# attinier85-power-shield-mk-1_0.net
KiCad netlist of a schematic drawn in EAGLE
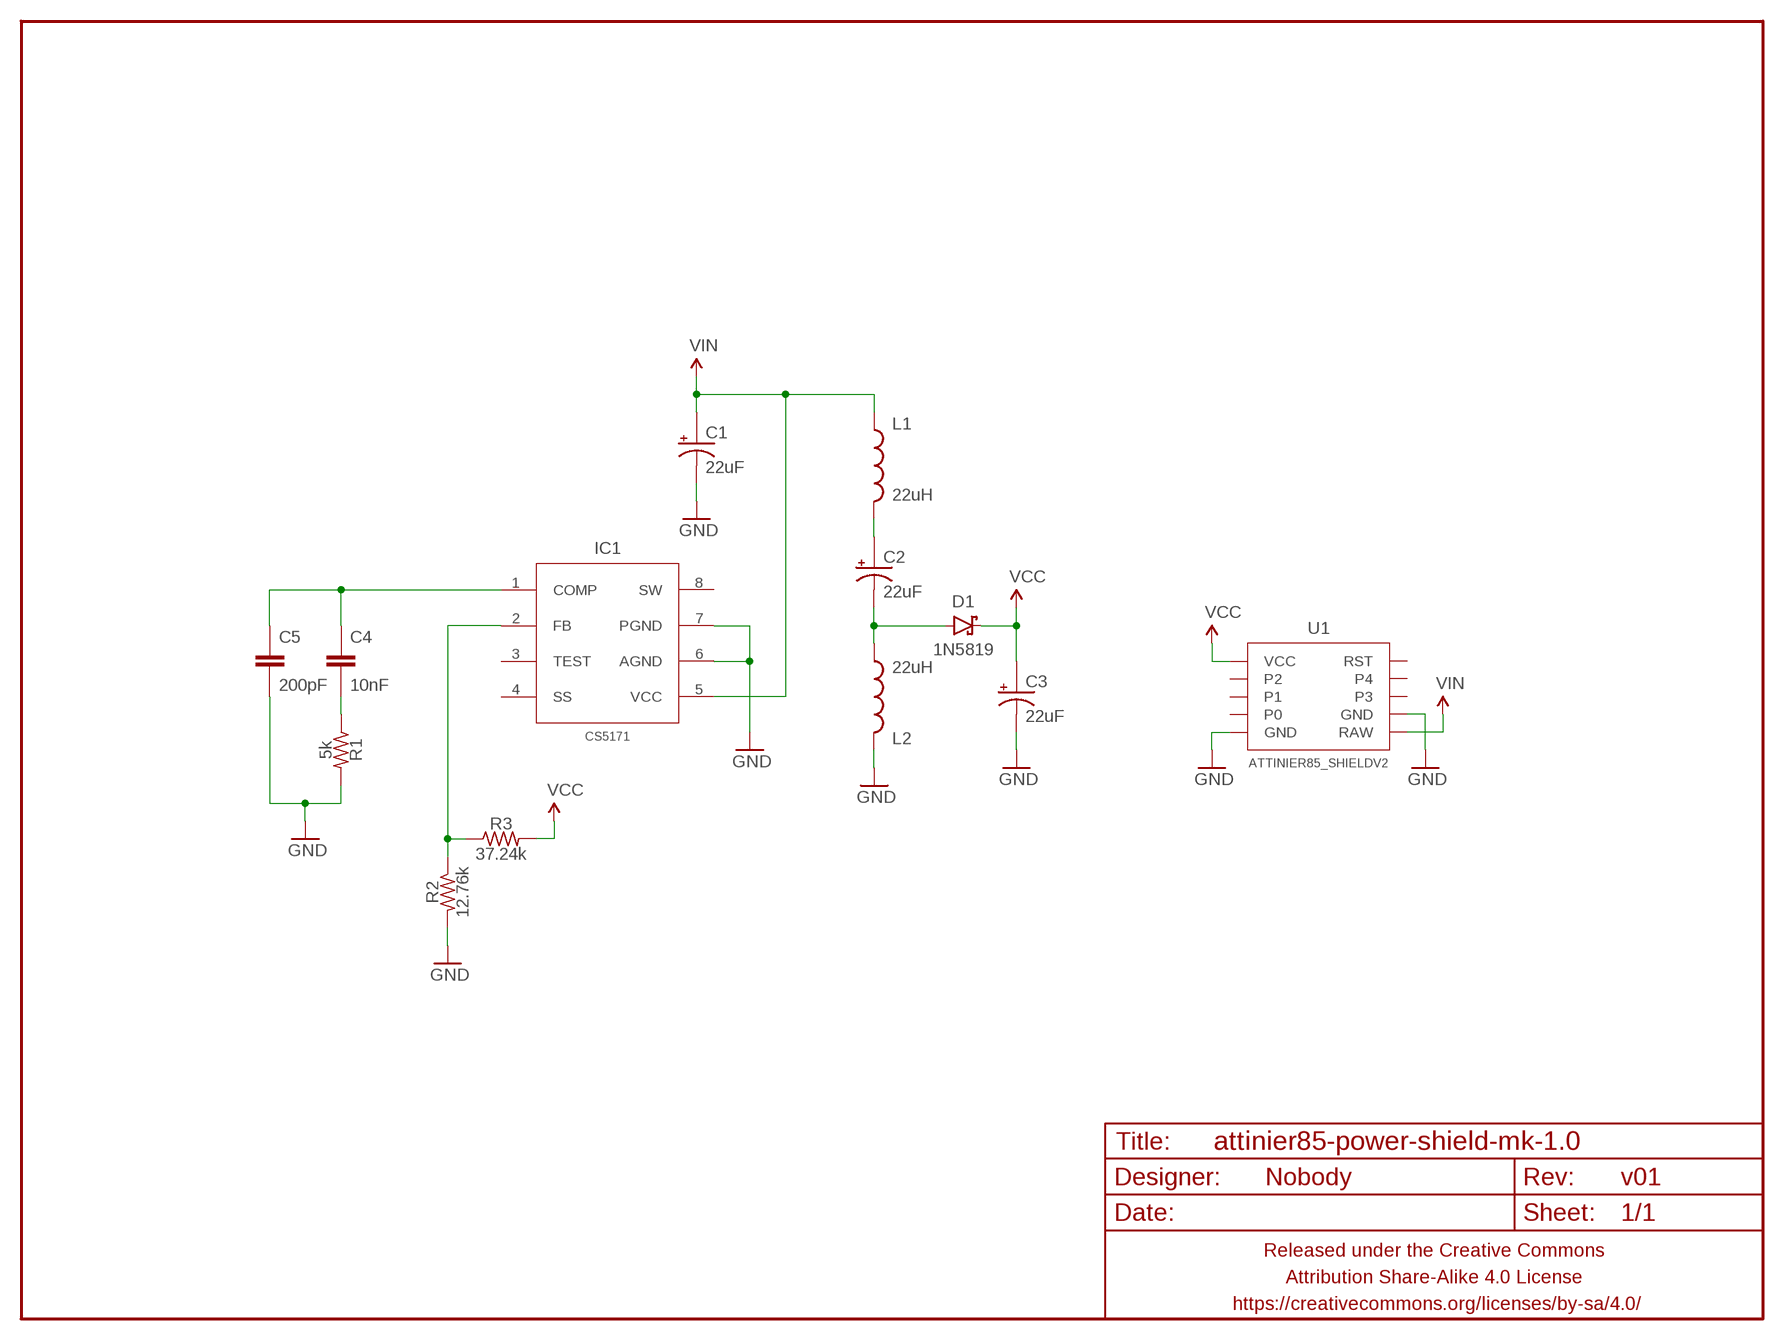
[diagram p0: schematic, sheet 1]

(export (version "E")
  (design (tool "Eeschema 10.0.6"))
  (components
    (comp (ref "C1")
      (value "22uF")
      (footprint "eagle-import:E2,5-6")
      (libsource (lib "eagle-import") (part "CAPACITOR-POLARIZEDE2.5-6"))
    )
    (comp (ref "C2")
      (value "22uF")
      (footprint "eagle-import:E2,5-6")
      (libsource (lib "eagle-import") (part "CAPACITOR-POLARIZEDE2.5-6"))
    )
    (comp (ref "C3")
      (value "22uF")
      (footprint "eagle-import:E2,5-6")
      (libsource (lib "eagle-import") (part "CAPACITOR-POLARIZEDE2.5-6"))
    )
    (comp (ref "C4")
      (value "10nF")
      (footprint "eagle-import:C025-024X044")
      (libsource (lib "eagle-import") (part "CAPACITOR-CERAMIC025-024X044"))
    )
    (comp (ref "C5")
      (value "200pF")
      (footprint "eagle-import:C025-024X044")
      (libsource (lib "eagle-import") (part "CAPACITOR-CERAMIC025-024X044"))
    )
    (comp (ref "D1")
      (value "1N5819")
      (footprint "eagle-import:DIODE-10.16MM")
      (libsource (lib "eagle-import") (part "DIODE-SCHOTTKYPTH-10.16MM"))
    )
    (comp (ref "FRAME1")
      (value "FRAME-LETTERNO_PACKAGE")
      (footprint "eagle-import:DUMMY")
      (fields (field (name "DESIGNER") "Nobody"))
      (libsource (lib "eagle-import") (part "FRAME-LETTERNO_PACKAGE"))
    )
    (comp (ref "IC1")
      (value "CS5171")
      (footprint "eagle-import:SO08")
      (libsource (lib "eagle-import") (part "CS5171/3SOIC-CS5171"))
    )
    (comp (ref "L1")
      (value "22uH")
      (footprint "eagle-import:INDUCTOR-AXIAL-PTH-10.16MM")
      (libsource (lib "eagle-import") (part "INDUCTORAXIAL-PTH-10.16MM"))
    )
    (comp (ref "L2")
      (value "22uH")
      (footprint "eagle-import:INDUCTOR-AXIAL-PTH-10.16MM")
      (libsource (lib "eagle-import") (part "INDUCTORAXIAL-PTH-10.16MM"))
    )
    (comp (ref "R1")
      (value "5k")
      (footprint "eagle-import:RESISTOR-AXIAL-PTH-6.35MM")
      (libsource (lib "eagle-import") (part "RESISTORPTH-AXIAL-6.35MM"))
    )
    (comp (ref "R2")
      (value "12.76k")
      (footprint "eagle-import:RESISTOR-AXIAL-PTH-6.35MM")
      (libsource (lib "eagle-import") (part "RESISTORPTH-AXIAL-6.35MM"))
    )
    (comp (ref "R3")
      (value "37.24k")
      (footprint "eagle-import:RESISTOR-AXIAL-PTH-6.35MM")
      (libsource (lib "eagle-import") (part "RESISTORPTH-AXIAL-6.35MM"))
    )
    (comp (ref "U1")
      (value "ATTINIER85_SHIELDV2")
      (footprint "eagle-import:ATTINIER85_SHIELD_V2")
      (libsource (lib "eagle-import") (part "ATTINIER85_SHIELDV2"))
    )
  )
  (nets
    (net (code "1") (name "GND") (class "Default")
      (node (ref "C1") (pin "-") (pinfunction "-_-") (pintype "passive"))
      (node (ref "C3") (pin "-") (pinfunction "-_-") (pintype "passive"))
      (node (ref "C5") (pin "2") (pinfunction "2_2") (pintype "passive"))
      (node (ref "IC1") (pin "6") (pinfunction "AGND_6") (pintype "bidirectional"))
      (node (ref "IC1") (pin "7") (pinfunction "PGND_7") (pintype "bidirectional"))
      (node (ref "L2") (pin "P$1") (pinfunction "1_P$1") (pintype "passive"))
      (node (ref "R1") (pin "P$2") (pinfunction "2_P$2") (pintype "passive"))
      (node (ref "R2") (pin "P$2") (pinfunction "2_P$2") (pintype "passive"))
      (node (ref "U1") (pin "GND@1") (pinfunction "GND_GND@1") (pintype "bidirectional"))
      (node (ref "U1") (pin "GND@2") (pinfunction "GND_GND@2") (pintype "bidirectional"))
    )
    (net (code "2") (name "Net-(IC1-COMP)") (class "Default")
      (node (ref "C4") (pin "1") (pinfunction "1_1") (pintype "passive"))
      (node (ref "C5") (pin "1") (pinfunction "1_1") (pintype "passive"))
      (node (ref "IC1") (pin "1") (pinfunction "COMP_1") (pintype "bidirectional"))
    )
    (net (code "3") (name "Net-(IC1-FB)") (class "Default")
      (node (ref "IC1") (pin "2") (pinfunction "FB_2") (pintype "bidirectional"))
      (node (ref "R2") (pin "P$1") (pinfunction "1_P$1") (pintype "passive"))
      (node (ref "R3") (pin "P$1") (pinfunction "1_P$1") (pintype "passive"))
    )
    (net (code "4") (name "Net-(L1-2)") (class "Default")
      (node (ref "C2") (pin "+") (pinfunction "+_+") (pintype "passive"))
      (node (ref "L1") (pin "P$2") (pinfunction "2_P$2") (pintype "passive"))
    )
    (net (code "5") (name "Net-(L2-2)") (class "Default")
      (node (ref "C2") (pin "-") (pinfunction "-_-") (pintype "passive"))
      (node (ref "D1") (pin "A") (pinfunction "A_A") (pintype "passive"))
      (node (ref "L2") (pin "P$2") (pinfunction "2_P$2") (pintype "passive"))
    )
    (net (code "6") (name "Net-(R1-1)") (class "Default")
      (node (ref "C4") (pin "2") (pinfunction "2_2") (pintype "passive"))
      (node (ref "R1") (pin "P$1") (pinfunction "1_P$1") (pintype "passive"))
    )
    (net (code "7") (name "VCC") (class "Default")
      (node (ref "C3") (pin "+") (pinfunction "+_+") (pintype "passive"))
      (node (ref "D1") (pin "C") (pinfunction "C_C") (pintype "passive"))
      (node (ref "R3") (pin "P$2") (pinfunction "2_P$2") (pintype "passive"))
      (node (ref "U1") (pin "VCC") (pinfunction "VCC_VCC") (pintype "bidirectional"))
    )
    (net (code "8") (name "VIN") (class "Default")
      (node (ref "C1") (pin "+") (pinfunction "+_+") (pintype "passive"))
      (node (ref "IC1") (pin "5") (pinfunction "VCC_5") (pintype "bidirectional"))
      (node (ref "L1") (pin "P$1") (pinfunction "1_P$1") (pintype "passive"))
      (node (ref "U1") (pin "RAW") (pinfunction "RAW_RAW") (pintype "bidirectional"))
    )
    (net (code "9") (name "unconnected-(IC1-SS-Pad4)") (class "Default")
      (node (ref "IC1") (pin "4") (pinfunction "SS_4") (pintype "bidirectional"))
    )
    (net (code "10") (name "unconnected-(IC1-SW-Pad8)") (class "Default")
      (node (ref "IC1") (pin "8") (pinfunction "SW_8") (pintype "bidirectional"))
    )
    (net (code "11") (name "unconnected-(IC1-TEST-Pad3)") (class "Default")
      (node (ref "IC1") (pin "3") (pinfunction "TEST_3") (pintype "bidirectional"))
    )
    (net (code "12") (name "unconnected-(U1-P0-Pad0)") (class "Default")
      (node (ref "U1") (pin "0") (pinfunction "P0_0") (pintype "bidirectional"))
    )
    (net (code "13") (name "unconnected-(U1-P1-Pad1)") (class "Default")
      (node (ref "U1") (pin "1") (pinfunction "P1_1") (pintype "bidirectional"))
    )
    (net (code "14") (name "unconnected-(U1-P2-Pad2)") (class "Default")
      (node (ref "U1") (pin "2") (pinfunction "P2_2") (pintype "bidirectional"))
    )
    (net (code "15") (name "unconnected-(U1-P3-Pad3)") (class "Default")
      (node (ref "U1") (pin "3") (pinfunction "P3_3") (pintype "bidirectional"))
    )
    (net (code "16") (name "unconnected-(U1-P4-Pad4)") (class "Default")
      (node (ref "U1") (pin "4") (pinfunction "P4_4") (pintype "bidirectional"))
    )
    (net (code "17") (name "unconnected-(U1-PadRST)") (class "Default")
      (node (ref "U1") (pin "RST") (pinfunction "RST_RST") (pintype "bidirectional"))
    )
  )
)
